# LDBiasDriver.net
KiCad netlist of a schematic drawn in EAGLE
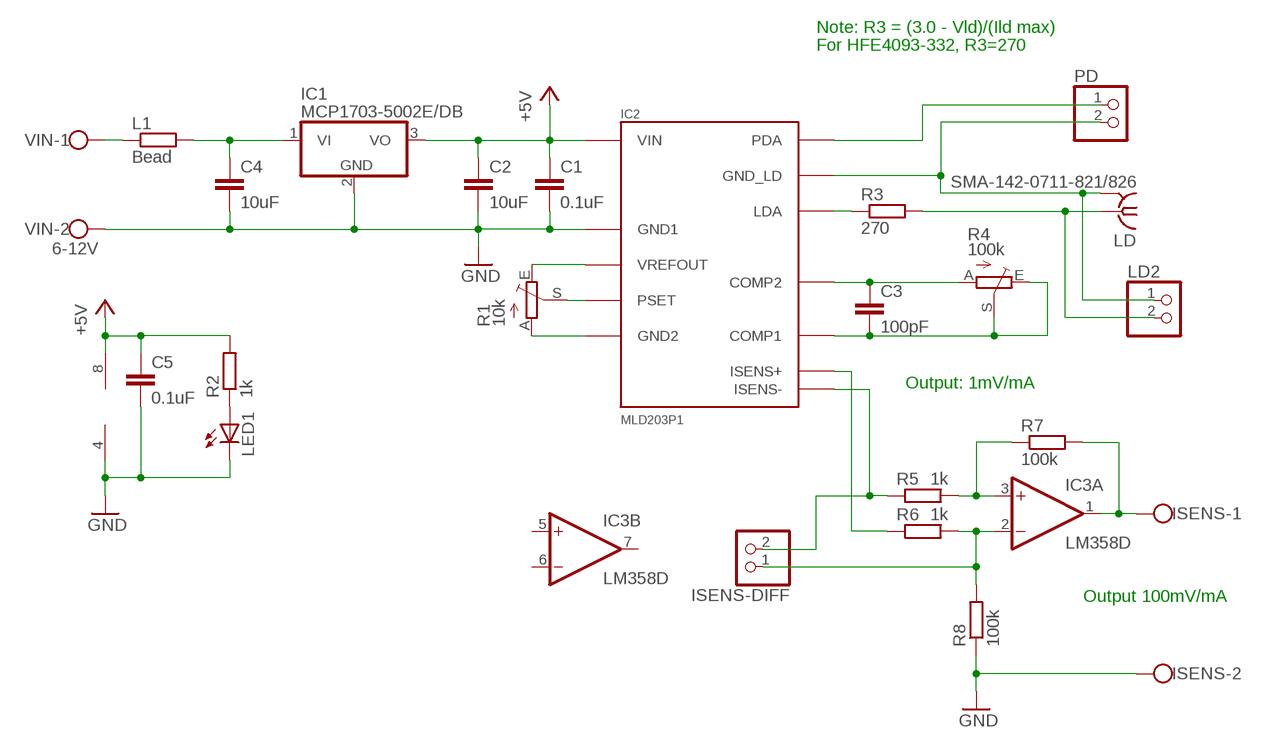
[diagram p0: schematic, sheet 1]

(export (version "E")
  (design (tool "Eeschema 10.0.6"))
  (components
    (comp (ref "C1")
      (value "0.1uF")
      (footprint "eagle-import:C0805")
      (libsource (lib "eagle-import") (part "C-EUC0805"))
    )
    (comp (ref "C2")
      (value "10uF")
      (footprint "eagle-import:C0805")
      (libsource (lib "eagle-import") (part "C-EUC0805"))
    )
    (comp (ref "C3")
      (value "100pF")
      (footprint "eagle-import:C0805")
      (libsource (lib "eagle-import") (part "C-EUC0805"))
    )
    (comp (ref "C4")
      (value "10uF")
      (footprint "eagle-import:C0805")
      (libsource (lib "eagle-import") (part "C-EUC0805"))
    )
    (comp (ref "C5")
      (value "0.1uF")
      (footprint "eagle-import:C0805")
      (libsource (lib "eagle-import") (part "C-EUC0805"))
    )
    (comp (ref "IC1")
      (value "MCP1703-5002E/DB")
      (footprint "eagle-import:SOT223")
      (libsource (lib "eagle-import") (part "MCP1703DB"))
    )
    (comp (ref "IC2")
      (value "MLD203P1")
      (footprint "eagle-import:MLD203")
      (libsource (lib "eagle-import") (part "MLD203P1"))
    )
    (comp (ref "IC3")
      (value "LM358D")
      (footprint "eagle-import:SO08")
      (libsource (lib "eagle-import") (part "LM358D"))
    )
    (comp (ref "ISENS")
      (value "W237-102")
      (footprint "eagle-import:W237-102")
      (fields (field (name "MPN") "237-102"))
      (libsource (lib "eagle-import") (part "W237-102"))
    )
    (comp (ref "ISENS-DIFF")
      (value "PINHD-1X2")
      (footprint "eagle-import:1X02")
      (libsource (lib "eagle-import") (part "PINHD-1X2"))
    )
    (comp (ref "L1")
      (value "Bead")
      (footprint "eagle-import:R0805")
      (libsource (lib "eagle-import") (part "R-EU_R0805"))
    )
    (comp (ref "LD")
      (value "SMA-142-0711-821/826")
      (footprint "eagle-import:J502-ND-142-0711-821_826")
      (fields (field (name "MF") "JOHNSON COMPONENTS") (field (name "MPN") "142-0711-821"))
      (libsource (lib "eagle-import") (part "SMA-142-0711-821/826"))
    )
    (comp (ref "LD2")
      (value "PINHD-1X2")
      (footprint "eagle-import:1X02")
      (libsource (lib "eagle-import") (part "PINHD-1X2"))
    )
    (comp (ref "LED1")
      (value "LEDCHIPLED_1206")
      (footprint "eagle-import:CHIPLED_1206")
      (libsource (lib "eagle-import") (part "LEDCHIPLED_1206"))
    )
    (comp (ref "PD")
      (value "PINHD-1X2")
      (footprint "eagle-import:1X02")
      (libsource (lib "eagle-import") (part "PINHD-1X2"))
    )
    (comp (ref "R1")
      (value "10k")
      (footprint "eagle-import:RJ9W")
      (libsource (lib "eagle-import") (part "TRIM_EU-RJ9W"))
    )
    (comp (ref "R2")
      (value "1k")
      (footprint "eagle-import:R0805")
      (libsource (lib "eagle-import") (part "R-EU_R0805"))
    )
    (comp (ref "R3")
      (value "270")
      (footprint "eagle-import:R0805")
      (libsource (lib "eagle-import") (part "R-EU_R0805"))
    )
    (comp (ref "R4")
      (value "100k")
      (footprint "eagle-import:RJ9W")
      (libsource (lib "eagle-import") (part "TRIM_EU-RJ9W"))
    )
    (comp (ref "R5")
      (value "1k")
      (footprint "eagle-import:R0805")
      (libsource (lib "eagle-import") (part "R-EU_R0805"))
    )
    (comp (ref "R6")
      (value "1k")
      (footprint "eagle-import:R0805")
      (libsource (lib "eagle-import") (part "R-EU_R0805"))
    )
    (comp (ref "R7")
      (value "100k")
      (footprint "eagle-import:R0805")
      (libsource (lib "eagle-import") (part "R-EU_R0805"))
    )
    (comp (ref "R8")
      (value "100k")
      (footprint "eagle-import:R0805")
      (libsource (lib "eagle-import") (part "R-EU_R0805"))
    )
    (comp (ref "VIN")
      (value "6-12V")
      (footprint "eagle-import:W237-102")
      (fields (field (name "MPN") "237-102"))
      (libsource (lib "eagle-import") (part "W237-102"))
    )
  )
  (nets
    (net (code "1") (name "+5V") (class "Default")
      (node (ref "C1") (pin "1") (pinfunction "1_1") (pintype "passive"))
      (node (ref "C2") (pin "1") (pinfunction "1_1") (pintype "passive"))
      (node (ref "C5") (pin "1") (pinfunction "1_1") (pintype "passive"))
      (node (ref "IC1") (pin "3") (pinfunction "VO_3") (pintype "passive"))
      (node (ref "IC2") (pin "P$1") (pinfunction "VIN_P$1") (pintype "power_in"))
      (node (ref "IC2") (pin "P$2") (pinfunction "VIN_P$2") (pintype "power_in"))
      (node (ref "IC3") (pin "8") (pinfunction "V+_8") (pintype "power_in"))
      (node (ref "R2") (pin "2") (pinfunction "2_2") (pintype "passive"))
    )
    (net (code "2") (name "GND") (class "Default")
      (node (ref "C1") (pin "2") (pinfunction "2_2") (pintype "passive"))
      (node (ref "C2") (pin "2") (pinfunction "2_2") (pintype "passive"))
      (node (ref "C4") (pin "2") (pinfunction "2_2") (pintype "passive"))
      (node (ref "C5") (pin "2") (pinfunction "2_2") (pintype "passive"))
      (node (ref "IC1") (pin "2") (pinfunction "GND_2") (pintype "passive"))
      (node (ref "IC2") (pin "P$3") (pinfunction "GND1_P$3") (pintype "power_in"))
      (node (ref "IC3") (pin "4") (pinfunction "V-_4") (pintype "power_in"))
      (node (ref "ISENS") (pin "2") (pinfunction "KL_2") (pintype "passive"))
      (node (ref "LED1") (pin "C") (pinfunction "C_C") (pintype "passive"))
      (node (ref "R8") (pin "1") (pinfunction "1_1") (pintype "passive"))
      (node (ref "VIN") (pin "2") (pinfunction "KL_2") (pintype "passive"))
    )
    (net (code "3") (name "Net-(IC1-VI)") (class "Default")
      (node (ref "C4") (pin "1") (pinfunction "1_1") (pintype "passive"))
      (node (ref "IC1") (pin "1") (pinfunction "VI_1") (pintype "input"))
      (node (ref "L1") (pin "2") (pinfunction "2_2") (pintype "passive"))
    )
    (net (code "4") (name "Net-(IC2-COMP1)") (class "Default")
      (node (ref "C3") (pin "2") (pinfunction "2_2") (pintype "passive"))
      (node (ref "IC2") (pin "P$10") (pinfunction "COMP1_P$10") (pintype "bidirectional"))
      (node (ref "R4") (pin "E") (pinfunction "E_E") (pintype "passive"))
      (node (ref "R4") (pin "S") (pinfunction "S_S") (pintype "passive"))
    )
    (net (code "5") (name "Net-(IC2-COMP2)") (class "Default")
      (node (ref "C3") (pin "1") (pinfunction "1_1") (pintype "passive"))
      (node (ref "IC2") (pin "P$9") (pinfunction "COMP2_P$9") (pintype "bidirectional"))
      (node (ref "R4") (pin "A") (pinfunction "A_A") (pintype "passive"))
    )
    (net (code "6") (name "Net-(IC2-GND2)") (class "Default")
      (node (ref "IC2") (pin "P$4") (pinfunction "GND2_P$4") (pintype "power_in"))
      (node (ref "R1") (pin "A") (pinfunction "A_A") (pintype "passive"))
    )
    (net (code "7") (name "Net-(IC2-GND_LD)") (class "Default")
      (node (ref "IC2") (pin "P$11") (pinfunction "GND_LD_P$11") (pintype "bidirectional"))
      (node (ref "LD") (pin "G@1") (pinfunction "2_G@1") (pintype "passive"))
      (node (ref "LD") (pin "G@2") (pinfunction "2_G@2") (pintype "passive"))
      (node (ref "LD") (pin "G@3") (pinfunction "2_G@3") (pintype "passive"))
      (node (ref "LD") (pin "G@4") (pinfunction "2_G@4") (pintype "passive"))
      (node (ref "LD2") (pin "1") (pinfunction "1_1") (pintype "passive"))
      (node (ref "PD") (pin "2") (pinfunction "2_2") (pintype "passive"))
    )
    (net (code "8") (name "Net-(IC2-ISENS+)") (class "Default")
      (node (ref "IC2") (pin "P$12") (pinfunction "ISENS+_P$12") (pintype "bidirectional"))
      (node (ref "R6") (pin "1") (pinfunction "1_1") (pintype "passive"))
    )
    (net (code "9") (name "Net-(IC2-ISENS-)") (class "Default")
      (node (ref "IC2") (pin "P$13") (pinfunction "ISENS-_P$13") (pintype "bidirectional"))
      (node (ref "ISENS-DIFF") (pin "2") (pinfunction "2_2") (pintype "passive"))
      (node (ref "R5") (pin "1") (pinfunction "1_1") (pintype "passive"))
    )
    (net (code "10") (name "Net-(IC2-LDA)") (class "Default")
      (node (ref "IC2") (pin "P$14") (pinfunction "LDA_P$14") (pintype "bidirectional"))
      (node (ref "R3") (pin "1") (pinfunction "1_1") (pintype "passive"))
    )
    (net (code "11") (name "Net-(IC2-PDA)") (class "Default")
      (node (ref "IC2") (pin "P$8") (pinfunction "PDA_P$8") (pintype "bidirectional"))
      (node (ref "PD") (pin "1") (pinfunction "1_1") (pintype "passive"))
    )
    (net (code "12") (name "Net-(IC2-PSET)") (class "Default")
      (node (ref "IC2") (pin "P$6") (pinfunction "PSET_P$6") (pintype "bidirectional"))
      (node (ref "R1") (pin "S") (pinfunction "S_S") (pintype "passive"))
    )
    (net (code "13") (name "Net-(IC2-VREFOUT)") (class "Default")
      (node (ref "IC2") (pin "P$5") (pinfunction "VREFOUT_P$5") (pintype "bidirectional"))
      (node (ref "R1") (pin "E") (pinfunction "E_E") (pintype "passive"))
    )
    (net (code "14") (name "Net-(IC3A-+IN)") (class "Default")
      (node (ref "IC3") (pin "3") (pinfunction "+IN_3") (pintype "input"))
      (node (ref "R5") (pin "2") (pinfunction "2_2") (pintype "passive"))
      (node (ref "R7") (pin "1") (pinfunction "1_1") (pintype "passive"))
    )
    (net (code "15") (name "Net-(IC3A--IN)") (class "Default")
      (node (ref "IC3") (pin "2") (pinfunction "-IN_2") (pintype "input"))
      (node (ref "ISENS-DIFF") (pin "1") (pinfunction "1_1") (pintype "passive"))
      (node (ref "R6") (pin "2") (pinfunction "2_2") (pintype "passive"))
      (node (ref "R8") (pin "2") (pinfunction "2_2") (pintype "passive"))
    )
    (net (code "16") (name "Net-(IC3A-OUT)") (class "Default")
      (node (ref "IC3") (pin "1") (pinfunction "OUT_1") (pintype "output"))
      (node (ref "ISENS") (pin "1") (pinfunction "KL_1") (pintype "passive"))
      (node (ref "R7") (pin "2") (pinfunction "2_2") (pintype "passive"))
    )
    (net (code "17") (name "Net-(LD-Pad1)") (class "Default")
      (node (ref "LD") (pin "1") (pinfunction "1_1") (pintype "passive"))
      (node (ref "LD2") (pin "2") (pinfunction "2_2") (pintype "passive"))
      (node (ref "R3") (pin "2") (pinfunction "2_2") (pintype "passive"))
    )
    (net (code "18") (name "Net-(LED1-PadA)") (class "Default")
      (node (ref "LED1") (pin "A") (pinfunction "A_A") (pintype "passive"))
      (node (ref "R2") (pin "1") (pinfunction "1_1") (pintype "passive"))
    )
    (net (code "19") (name "Net-(VINA-KL)") (class "Default")
      (node (ref "L1") (pin "1") (pinfunction "1_1") (pintype "passive"))
      (node (ref "VIN") (pin "1") (pinfunction "KL_1") (pintype "passive"))
    )
    (net (code "20") (name "unconnected-(IC3B-+IN-Pad5)") (class "Default")
      (node (ref "IC3") (pin "5") (pinfunction "+IN_5") (pintype "input"))
    )
    (net (code "21") (name "unconnected-(IC3B--IN-Pad6)") (class "Default")
      (node (ref "IC3") (pin "6") (pinfunction "-IN_6") (pintype "input"))
    )
    (net (code "22") (name "unconnected-(IC3B-OUT-Pad7)") (class "Default")
      (node (ref "IC3") (pin "7") (pinfunction "OUT_7") (pintype "output"))
    )
  )
)
